# uacs-bottom.net
KiCad netlist of a schematic drawn in EAGLE
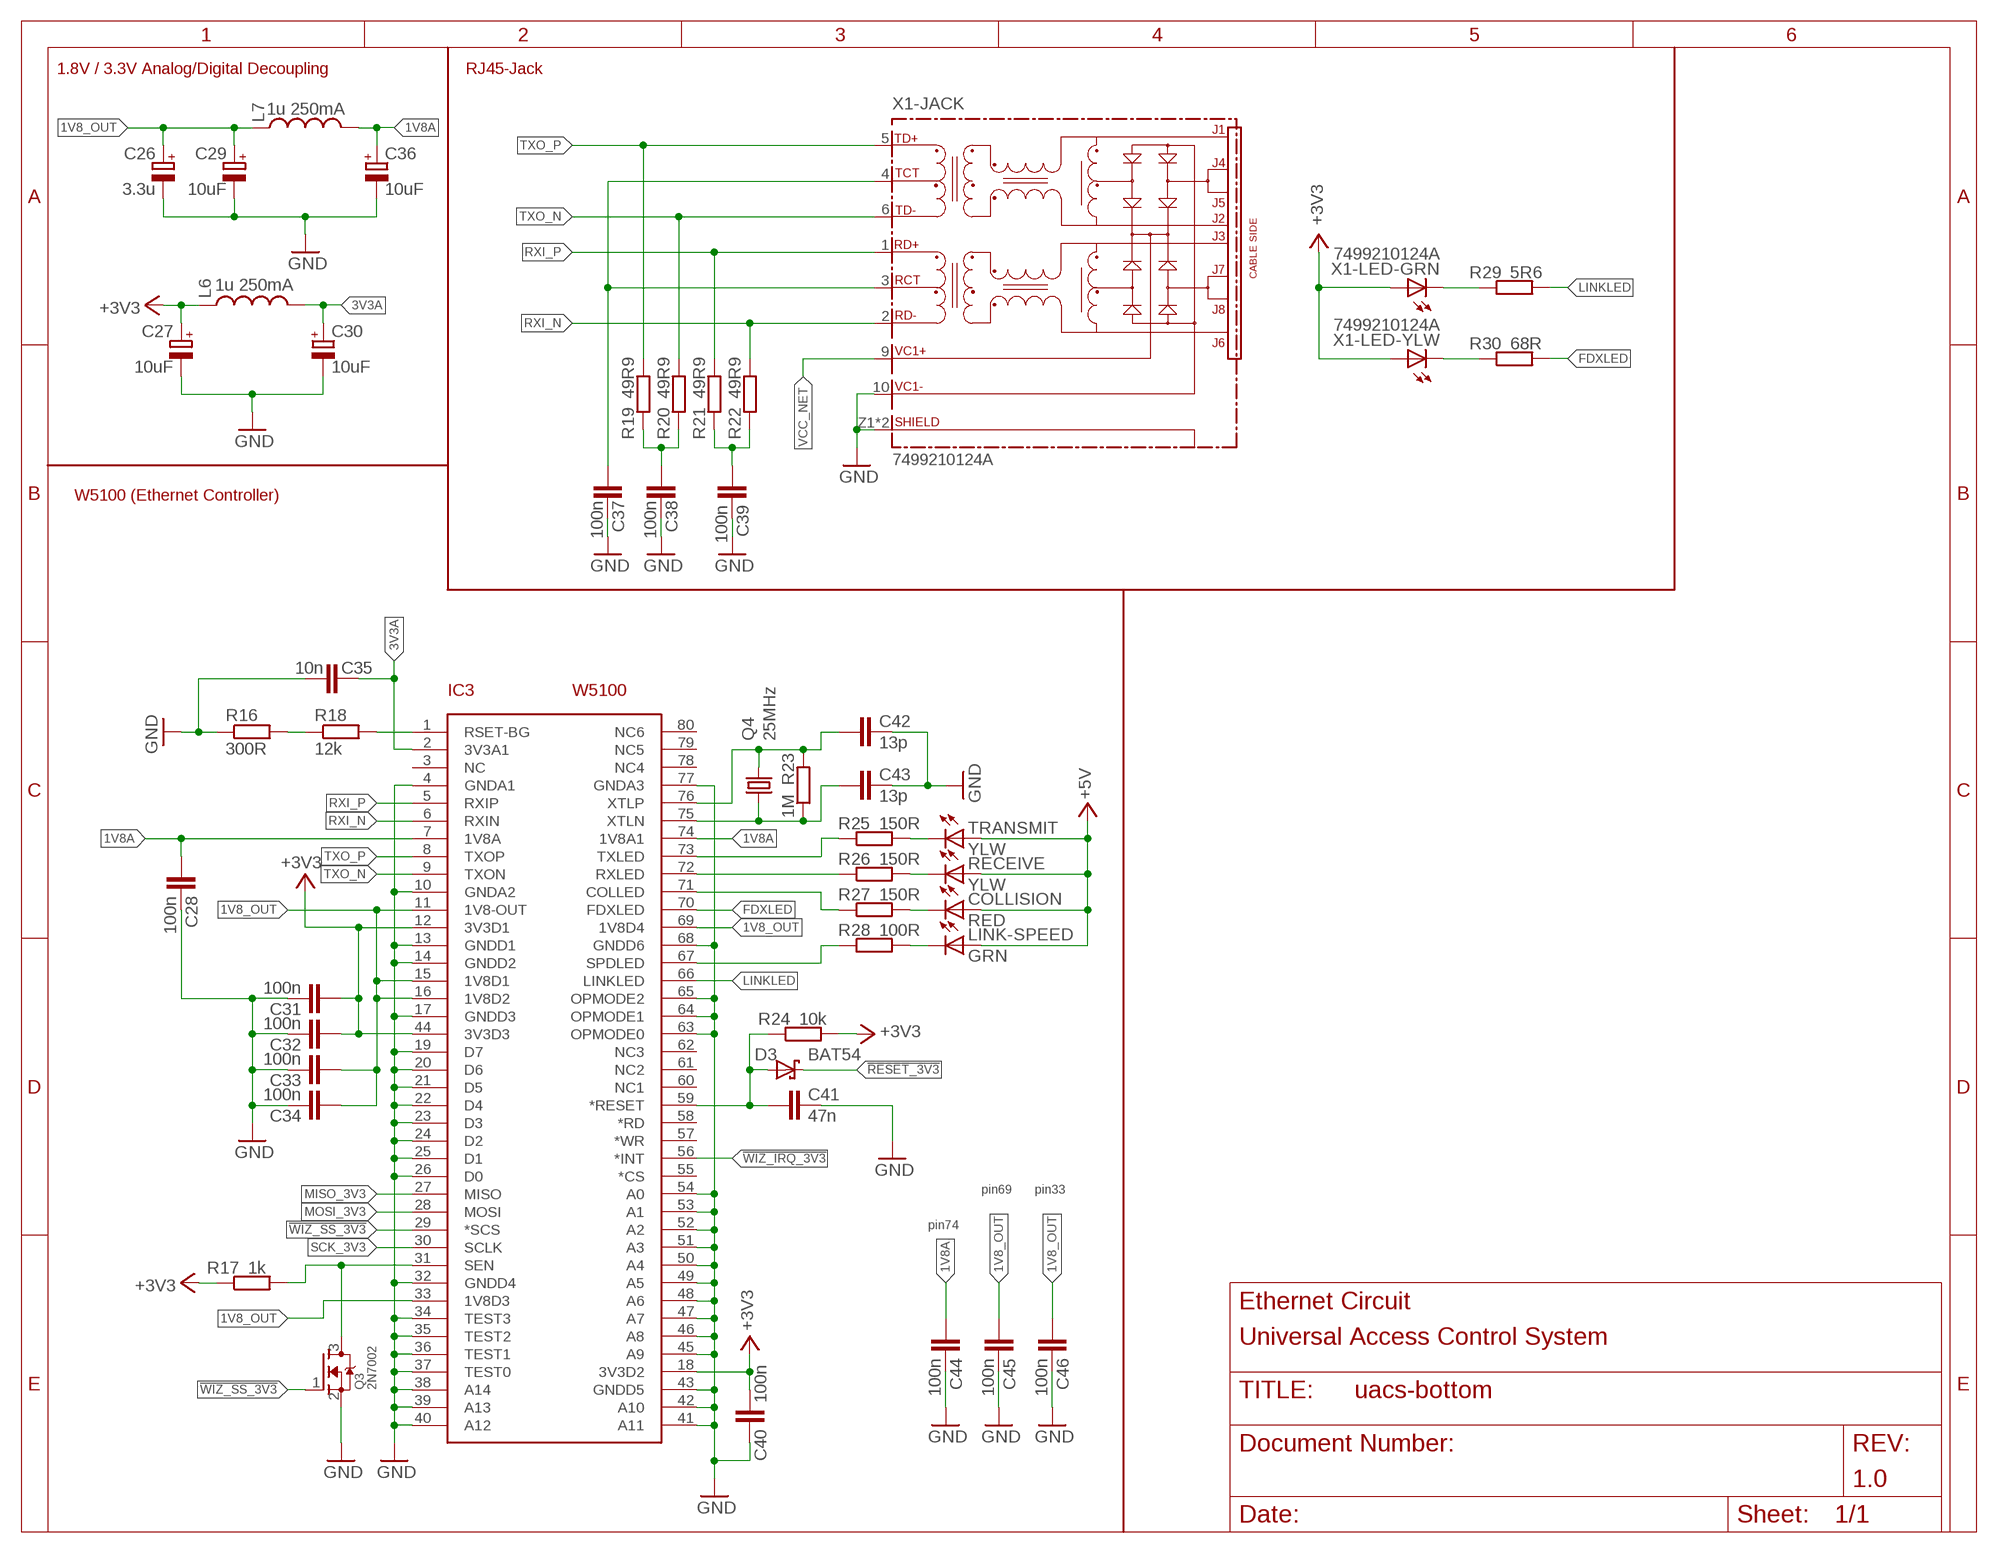
[diagram p0: schematic, sheet 1]

(export (version "E")
  (design (tool "Eeschema 10.0.6"))
  (components
    (comp (ref "C26")
      (value "3.3u")
      (footprint "eagle-import:B_3528-21R")
      (libsource (lib "eagle-import") (part "CPOL-EUB/3528-21R"))
    )
    (comp (ref "C27")
      (value "10uF")
      (footprint "eagle-import:B_3528-21R")
      (libsource (lib "eagle-import") (part "CPOL-EUB/3528-21R"))
    )
    (comp (ref "C28")
      (value "100n")
      (footprint "eagle-import:C0603")
      (libsource (lib "eagle-import") (part "C-EUC0603"))
    )
    (comp (ref "C29")
      (value "10uF")
      (footprint "eagle-import:B_3528-21R")
      (libsource (lib "eagle-import") (part "CPOL-EUB/3528-21R"))
    )
    (comp (ref "C30")
      (value "10uF")
      (footprint "eagle-import:B_3528-21R")
      (libsource (lib "eagle-import") (part "CPOL-EUB/3528-21R"))
    )
    (comp (ref "C31")
      (value "100n")
      (footprint "eagle-import:C0603")
      (libsource (lib "eagle-import") (part "C-EUC0603"))
    )
    (comp (ref "C32")
      (value "100n")
      (footprint "eagle-import:C0603")
      (libsource (lib "eagle-import") (part "C-EUC0603"))
    )
    (comp (ref "C33")
      (value "100n")
      (footprint "eagle-import:C0603")
      (libsource (lib "eagle-import") (part "C-EUC0603"))
    )
    (comp (ref "C34")
      (value "100n")
      (footprint "eagle-import:C0603")
      (libsource (lib "eagle-import") (part "C-EUC0603"))
    )
    (comp (ref "C35")
      (value "10n")
      (footprint "eagle-import:C0603")
      (libsource (lib "eagle-import") (part "C-EUC0603"))
    )
    (comp (ref "C36")
      (value "10uF")
      (footprint "eagle-import:B_3528-21R")
      (libsource (lib "eagle-import") (part "CPOL-EUB/3528-21R"))
    )
    (comp (ref "C37")
      (value "100n")
      (footprint "eagle-import:C0603")
      (libsource (lib "eagle-import") (part "C-EUC0603"))
    )
    (comp (ref "C38")
      (value "100n")
      (footprint "eagle-import:C0603")
      (libsource (lib "eagle-import") (part "C-EUC0603"))
    )
    (comp (ref "C39")
      (value "100n")
      (footprint "eagle-import:C0603")
      (libsource (lib "eagle-import") (part "C-EUC0603"))
    )
    (comp (ref "C40")
      (value "100n")
      (footprint "eagle-import:C0603")
      (libsource (lib "eagle-import") (part "C-EUC0603"))
    )
    (comp (ref "C41")
      (value "47n")
      (footprint "eagle-import:C0603")
      (libsource (lib "eagle-import") (part "C-EUC0603"))
    )
    (comp (ref "C42")
      (value "13p")
      (footprint "eagle-import:C0603")
      (libsource (lib "eagle-import") (part "C-EUC0603"))
    )
    (comp (ref "C43")
      (value "13p")
      (footprint "eagle-import:C0603")
      (libsource (lib "eagle-import") (part "C-EUC0603"))
    )
    (comp (ref "C44")
      (value "100n")
      (footprint "eagle-import:C0603")
      (libsource (lib "eagle-import") (part "C-EUC0603"))
    )
    (comp (ref "C45")
      (value "100n")
      (footprint "eagle-import:C0603")
      (libsource (lib "eagle-import") (part "C-EUC0603"))
    )
    (comp (ref "C46")
      (value "100n")
      (footprint "eagle-import:C0603")
      (libsource (lib "eagle-import") (part "C-EUC0603"))
    )
    (comp (ref "COLLISION")
      (value "RED")
      (footprint "eagle-import:CHIPLED_0603")
      (libsource (lib "eagle-import") (part "LEDCHIPLED_0603"))
    )
    (comp (ref "D3")
      (value "BAT54")
      (footprint "eagle-import:SOT23")
      (libsource (lib "eagle-import") (part "BAT54"))
    )
    (comp (ref "IC3")
      (value "W5100")
      (footprint "eagle-import:SQFP-S-10X10-80")
      (libsource (lib "eagle-import") (part "W5100"))
    )
    (comp (ref "L6")
      (value "1u 250mA")
      (footprint "eagle-import:0603")
      (libsource (lib "eagle-import") (part "INDUCTOR0603"))
    )
    (comp (ref "L7")
      (value "1u 250mA")
      (footprint "eagle-import:0603")
      (libsource (lib "eagle-import") (part "INDUCTOR0603"))
    )
    (comp (ref "LINK-SPEED")
      (value "GRN")
      (footprint "eagle-import:CHIPLED_0603")
      (libsource (lib "eagle-import") (part "LEDCHIPLED_0603"))
    )
    (comp (ref "Q3")
      (value "2N7002")
      (footprint "eagle-import:SOT23")
      (libsource (lib "eagle-import") (part "MOSFET-NREFLOW"))
    )
    (comp (ref "Q4")
      (value "25MHz")
      (footprint "eagle-import:SM49")
      (libsource (lib "eagle-import") (part "CRYSTALSM49"))
    )
    (comp (ref "R16")
      (value "300R")
      (footprint "eagle-import:R0603")
      (libsource (lib "eagle-import") (part "R-EU_R0603"))
    )
    (comp (ref "R17")
      (value "1k")
      (footprint "eagle-import:R0603")
      (libsource (lib "eagle-import") (part "R-EU_R0603"))
    )
    (comp (ref "R18")
      (value "12k")
      (footprint "eagle-import:R0603")
      (libsource (lib "eagle-import") (part "R-EU_R0603"))
    )
    (comp (ref "R19")
      (value "49R9")
      (footprint "eagle-import:R0603")
      (libsource (lib "eagle-import") (part "R-EU_R0603"))
    )
    (comp (ref "R20")
      (value "49R9")
      (footprint "eagle-import:R0603")
      (libsource (lib "eagle-import") (part "R-EU_R0603"))
    )
    (comp (ref "R21")
      (value "49R9")
      (footprint "eagle-import:R0603")
      (libsource (lib "eagle-import") (part "R-EU_R0603"))
    )
    (comp (ref "R22")
      (value "49R9")
      (footprint "eagle-import:R0603")
      (libsource (lib "eagle-import") (part "R-EU_R0603"))
    )
    (comp (ref "R23")
      (value "1M")
      (footprint "eagle-import:R0603")
      (libsource (lib "eagle-import") (part "R-EU_R0603"))
    )
    (comp (ref "R24")
      (value "10k")
      (footprint "eagle-import:R0603")
      (libsource (lib "eagle-import") (part "R-EU_R0603"))
    )
    (comp (ref "R25")
      (value "150R")
      (footprint "eagle-import:R0603")
      (libsource (lib "eagle-import") (part "R-EU_R0603"))
    )
    (comp (ref "R26")
      (value "150R")
      (footprint "eagle-import:R0603")
      (libsource (lib "eagle-import") (part "R-EU_R0603"))
    )
    (comp (ref "R27")
      (value "150R")
      (footprint "eagle-import:R0603")
      (libsource (lib "eagle-import") (part "R-EU_R0603"))
    )
    (comp (ref "R28")
      (value "100R")
      (footprint "eagle-import:R0603")
      (libsource (lib "eagle-import") (part "R-EU_R0603"))
    )
    (comp (ref "R29")
      (value "5R6")
      (footprint "eagle-import:R0603")
      (libsource (lib "eagle-import") (part "R-EU_R0603"))
    )
    (comp (ref "R30")
      (value "68R")
      (footprint "eagle-import:R0603")
      (libsource (lib "eagle-import") (part "R-EU_R0603"))
    )
    (comp (ref "RECEIVE")
      (value "YLW")
      (footprint "eagle-import:CHIPLED_0603")
      (libsource (lib "eagle-import") (part "LEDCHIPLED_0603"))
    )
    (comp (ref "TRANSMIT")
      (value "YLW")
      (footprint "eagle-import:CHIPLED_0603")
      (libsource (lib "eagle-import") (part "LEDCHIPLED_0603"))
    )
    (comp (ref "X1")
      (value "7499210124A")
      (footprint "eagle-import:7499210124A")
      (libsource (lib "eagle-import") (part "7499210124A"))
    )
  )
  (nets
    (net (code "1") (name "+3V3") (class "Default")
      (node (ref "C27") (pin "+") (pinfunction "+_+") (pintype "passive"))
      (node (ref "C31") (pin "1") (pinfunction "1_1") (pintype "passive"))
      (node (ref "C32") (pin "1") (pinfunction "1_1") (pintype "passive"))
      (node (ref "C40") (pin "1") (pinfunction "1_1") (pintype "passive"))
      (node (ref "IC3") (pin "12") (pinfunction "3V3D1_12") (pintype "power_in"))
      (node (ref "IC3") (pin "18") (pinfunction "3V3D2_18") (pintype "power_in"))
      (node (ref "IC3") (pin "44") (pinfunction "3V3D3_44") (pintype "power_in"))
      (node (ref "L6") (pin "1") (pinfunction "1_1") (pintype "passive"))
      (node (ref "R17") (pin "1") (pinfunction "1_1") (pintype "passive"))
      (node (ref "R24") (pin "2") (pinfunction "2_2") (pintype "passive"))
      (node (ref "X1") (pin "12") (pinfunction "A_12") (pintype "passive"))
      (node (ref "X1") (pin "14") (pinfunction "A_14") (pintype "passive"))
    )
    (net (code "2") (name "+5V") (class "Default")
      (node (ref "COLLISION") (pin "A") (pinfunction "A_A") (pintype "passive"))
      (node (ref "LINK-SPEED") (pin "A") (pinfunction "A_A") (pintype "passive"))
      (node (ref "RECEIVE") (pin "A") (pinfunction "A_A") (pintype "passive"))
      (node (ref "TRANSMIT") (pin "A") (pinfunction "A_A") (pintype "passive"))
    )
    (net (code "3") (name "/~{RESET_3V3}") (class "Default")
      (node (ref "D3") (pin "3") (pinfunction "C_3") (pintype "passive"))
    )
    (net (code "4") (name "/~{WIZ_IRQ_3V3}") (class "Default")
      (node (ref "IC3") (pin "56") (pinfunction "*INT_56") (pintype "input"))
    )
    (net (code "5") (name "/~{WIZ_SS_3V3}") (class "Default")
      (node (ref "IC3") (pin "29") (pinfunction "*SCS_29") (pintype "input"))
      (node (ref "Q3") (pin "1") (pinfunction "G_1") (pintype "bidirectional"))
    )
    (net (code "6") (name "1V8A") (class "Default")
      (node (ref "C28") (pin "1") (pinfunction "1_1") (pintype "passive"))
      (node (ref "C36") (pin "+") (pinfunction "+_+") (pintype "passive"))
      (node (ref "C44") (pin "1") (pinfunction "1_1") (pintype "passive"))
      (node (ref "IC3") (pin "7") (pinfunction "1V8A_7") (pintype "power_in"))
      (node (ref "IC3") (pin "74") (pinfunction "1V8A1_74") (pintype "power_in"))
      (node (ref "L7") (pin "2") (pinfunction "2_2") (pintype "passive"))
    )
    (net (code "7") (name "1V8_OUT") (class "Default")
      (node (ref "C26") (pin "+") (pinfunction "+_+") (pintype "passive"))
      (node (ref "C29") (pin "+") (pinfunction "+_+") (pintype "passive"))
      (node (ref "C33") (pin "1") (pinfunction "1_1") (pintype "passive"))
      (node (ref "C34") (pin "1") (pinfunction "1_1") (pintype "passive"))
      (node (ref "C45") (pin "1") (pinfunction "1_1") (pintype "passive"))
      (node (ref "C46") (pin "1") (pinfunction "1_1") (pintype "passive"))
      (node (ref "IC3") (pin "11") (pinfunction "1V8-OUT_11") (pintype "power_in"))
      (node (ref "IC3") (pin "15") (pinfunction "1V8D1_15") (pintype "power_in"))
      (node (ref "IC3") (pin "16") (pinfunction "1V8D2_16") (pintype "power_in"))
      (node (ref "IC3") (pin "33") (pinfunction "1V8D3_33") (pintype "power_in"))
      (node (ref "IC3") (pin "69") (pinfunction "1V8D4_69") (pintype "power_in"))
      (node (ref "L7") (pin "1") (pinfunction "1_1") (pintype "passive"))
    )
    (net (code "8") (name "3V3A") (class "Default")
      (node (ref "C30") (pin "+") (pinfunction "+_+") (pintype "passive"))
      (node (ref "C35") (pin "1") (pinfunction "1_1") (pintype "passive"))
      (node (ref "IC3") (pin "2") (pinfunction "3V3A1_2") (pintype "power_in"))
      (node (ref "L6") (pin "2") (pinfunction "2_2") (pintype "passive"))
    )
    (net (code "9") (name "FDXLED") (class "Default")
      (node (ref "IC3") (pin "70") (pinfunction "FDXLED_70") (pintype "output"))
      (node (ref "R30") (pin "2") (pinfunction "2_2") (pintype "passive"))
    )
    (net (code "10") (name "GND") (class "Default")
      (node (ref "C26") (pin "-") (pinfunction "-_-") (pintype "passive"))
      (node (ref "C27") (pin "-") (pinfunction "-_-") (pintype "passive"))
      (node (ref "C28") (pin "2") (pinfunction "2_2") (pintype "passive"))
      (node (ref "C29") (pin "-") (pinfunction "-_-") (pintype "passive"))
      (node (ref "C30") (pin "-") (pinfunction "-_-") (pintype "passive"))
      (node (ref "C31") (pin "2") (pinfunction "2_2") (pintype "passive"))
      (node (ref "C32") (pin "2") (pinfunction "2_2") (pintype "passive"))
      (node (ref "C33") (pin "2") (pinfunction "2_2") (pintype "passive"))
      (node (ref "C34") (pin "2") (pinfunction "2_2") (pintype "passive"))
      (node (ref "C35") (pin "2") (pinfunction "2_2") (pintype "passive"))
      (node (ref "C36") (pin "-") (pinfunction "-_-") (pintype "passive"))
      (node (ref "C37") (pin "2") (pinfunction "2_2") (pintype "passive"))
      (node (ref "C38") (pin "2") (pinfunction "2_2") (pintype "passive"))
      (node (ref "C39") (pin "2") (pinfunction "2_2") (pintype "passive"))
      (node (ref "C40") (pin "2") (pinfunction "2_2") (pintype "passive"))
      (node (ref "C41") (pin "2") (pinfunction "2_2") (pintype "passive"))
      (node (ref "C42") (pin "2") (pinfunction "2_2") (pintype "passive"))
      (node (ref "C43") (pin "2") (pinfunction "2_2") (pintype "passive"))
      (node (ref "C44") (pin "2") (pinfunction "2_2") (pintype "passive"))
      (node (ref "C45") (pin "2") (pinfunction "2_2") (pintype "passive"))
      (node (ref "C46") (pin "2") (pinfunction "2_2") (pintype "passive"))
      (node (ref "IC3") (pin "10") (pinfunction "GNDA2_10") (pintype "power_in"))
      (node (ref "IC3") (pin "13") (pinfunction "GNDD1_13") (pintype "power_in"))
      (node (ref "IC3") (pin "14") (pinfunction "GNDD2_14") (pintype "power_in"))
      (node (ref "IC3") (pin "17") (pinfunction "GNDD3_17") (pintype "power_in"))
      (node (ref "IC3") (pin "19") (pinfunction "D7_19") (pintype "input"))
      (node (ref "IC3") (pin "20") (pinfunction "D6_20") (pintype "input"))
      (node (ref "IC3") (pin "21") (pinfunction "D5_21") (pintype "input"))
      (node (ref "IC3") (pin "22") (pinfunction "D4_22") (pintype "input"))
      (node (ref "IC3") (pin "23") (pinfunction "D3_23") (pintype "input"))
      (node (ref "IC3") (pin "24") (pinfunction "D2_24") (pintype "input"))
      (node (ref "IC3") (pin "25") (pinfunction "D1_25") (pintype "input"))
      (node (ref "IC3") (pin "26") (pinfunction "D0_26") (pintype "input"))
      (node (ref "IC3") (pin "32") (pinfunction "GNDD4_32") (pintype "power_in"))
      (node (ref "IC3") (pin "34") (pinfunction "TEST3_34") (pintype "input"))
      (node (ref "IC3") (pin "35") (pinfunction "TEST2_35") (pintype "input"))
      (node (ref "IC3") (pin "36") (pinfunction "TEST1_36") (pintype "input"))
      (node (ref "IC3") (pin "37") (pinfunction "TEST0_37") (pintype "input"))
      (node (ref "IC3") (pin "38") (pinfunction "A14_38") (pintype "input"))
      (node (ref "IC3") (pin "39") (pinfunction "A13_39") (pintype "input"))
      (node (ref "IC3") (pin "4") (pinfunction "GNDA1_4") (pintype "power_in"))
      (node (ref "IC3") (pin "40") (pinfunction "A12_40") (pintype "input"))
      (node (ref "IC3") (pin "41") (pinfunction "A11_41") (pintype "input"))
      (node (ref "IC3") (pin "42") (pinfunction "A10_42") (pintype "input"))
      (node (ref "IC3") (pin "43") (pinfunction "GNDD5_43") (pintype "power_in"))
      (node (ref "IC3") (pin "45") (pinfunction "A9_45") (pintype "input"))
      (node (ref "IC3") (pin "46") (pinfunction "A8_46") (pintype "input"))
      (node (ref "IC3") (pin "47") (pinfunction "A7_47") (pintype "input"))
      (node (ref "IC3") (pin "48") (pinfunction "A6_48") (pintype "input"))
      (node (ref "IC3") (pin "49") (pinfunction "A5_49") (pintype "input"))
      (node (ref "IC3") (pin "50") (pinfunction "A4_50") (pintype "input"))
      (node (ref "IC3") (pin "51") (pinfunction "A3_51") (pintype "input"))
      (node (ref "IC3") (pin "52") (pinfunction "A2_52") (pintype "input"))
      (node (ref "IC3") (pin "53") (pinfunction "A1_53") (pintype "input"))
      (node (ref "IC3") (pin "54") (pinfunction "A0_54") (pintype "input"))
      (node (ref "IC3") (pin "63") (pinfunction "OPMODE0_63") (pintype "input"))
      (node (ref "IC3") (pin "64") (pinfunction "OPMODE1_64") (pintype "input"))
      (node (ref "IC3") (pin "65") (pinfunction "OPMODE2_65") (pintype "input"))
      (node (ref "IC3") (pin "68") (pinfunction "GNDD6_68") (pintype "power_in"))
      (node (ref "IC3") (pin "77") (pinfunction "GNDA3_77") (pintype "power_in"))
      (node (ref "Q3") (pin "2") (pinfunction "S_2") (pintype "bidirectional"))
      (node (ref "R16") (pin "1") (pinfunction "1_1") (pintype "passive"))
      (node (ref "X1") (pin "10") (pinfunction "VC1-_10") (pintype "power_in"))
      (node (ref "X1") (pin "Z1") (pinfunction "SHIELD_Z1") (pintype "bidirectional"))
      (node (ref "X1") (pin "Z2") (pinfunction "SHIELD_Z2") (pintype "bidirectional"))
    )
    (net (code "11") (name "LINKLED") (class "Default")
      (node (ref "IC3") (pin "66") (pinfunction "LINKLED_66") (pintype "output"))
      (node (ref "R29") (pin "2") (pinfunction "2_2") (pintype "passive"))
    )
    (net (code "12") (name "MISO_3V3") (class "Default")
      (node (ref "IC3") (pin "27") (pinfunction "MISO_27") (pintype "input"))
    )
    (net (code "13") (name "MOSI_3V3") (class "Default")
      (node (ref "IC3") (pin "28") (pinfunction "MOSI_28") (pintype "output"))
    )
    (net (code "14") (name "Net-(C38-Pad1)") (class "Default")
      (node (ref "C38") (pin "1") (pinfunction "1_1") (pintype "passive"))
      (node (ref "R19") (pin "1") (pinfunction "1_1") (pintype "passive"))
      (node (ref "R20") (pin "1") (pinfunction "1_1") (pintype "passive"))
    )
    (net (code "15") (name "Net-(C39-Pad1)") (class "Default")
      (node (ref "C39") (pin "1") (pinfunction "1_1") (pintype "passive"))
      (node (ref "R21") (pin "1") (pinfunction "1_1") (pintype "passive"))
      (node (ref "R22") (pin "1") (pinfunction "1_1") (pintype "passive"))
    )
    (net (code "16") (name "Net-(COLLISION-PadC)") (class "Default")
      (node (ref "COLLISION") (pin "C") (pinfunction "C_C") (pintype "passive"))
      (node (ref "R27") (pin "2") (pinfunction "2_2") (pintype "passive"))
    )
    (net (code "17") (name "Net-(D3-A)") (class "Default")
      (node (ref "C41") (pin "1") (pinfunction "1_1") (pintype "passive"))
      (node (ref "D3") (pin "1") (pinfunction "A_1") (pintype "passive"))
      (node (ref "IC3") (pin "59") (pinfunction "*RESET_59") (pintype "input"))
      (node (ref "R24") (pin "1") (pinfunction "1_1") (pintype "passive"))
    )
    (net (code "18") (name "Net-(IC3-COLLED)") (class "Default")
      (node (ref "IC3") (pin "71") (pinfunction "COLLED_71") (pintype "output"))
      (node (ref "R27") (pin "1") (pinfunction "1_1") (pintype "passive"))
    )
    (net (code "19") (name "Net-(IC3-RSET-BG)") (class "Default")
      (node (ref "IC3") (pin "1") (pinfunction "RSET-BG_1") (pintype "input"))
      (node (ref "R18") (pin "2") (pinfunction "2_2") (pintype "passive"))
    )
    (net (code "20") (name "Net-(IC3-RXLED)") (class "Default")
      (node (ref "IC3") (pin "72") (pinfunction "RXLED_72") (pintype "output"))
      (node (ref "R26") (pin "1") (pinfunction "1_1") (pintype "passive"))
    )
    (net (code "21") (name "Net-(IC3-SEN)") (class "Default")
      (node (ref "IC3") (pin "31") (pinfunction "SEN_31") (pintype "input"))
      (node (ref "Q3") (pin "3") (pinfunction "D_3") (pintype "bidirectional"))
      (node (ref "R17") (pin "2") (pinfunction "2_2") (pintype "passive"))
    )
    (net (code "22") (name "Net-(IC3-SPDLED)") (class "Default")
      (node (ref "IC3") (pin "67") (pinfunction "SPDLED_67") (pintype "output"))
      (node (ref "R28") (pin "1") (pinfunction "1_1") (pintype "passive"))
    )
    (net (code "23") (name "Net-(IC3-TXLED)") (class "Default")
      (node (ref "IC3") (pin "73") (pinfunction "TXLED_73") (pintype "output"))
      (node (ref "R25") (pin "1") (pinfunction "1_1") (pintype "passive"))
    )
    (net (code "24") (name "Net-(IC3-XTLN)") (class "Default")
      (node (ref "C43") (pin "1") (pinfunction "1_1") (pintype "passive"))
      (node (ref "IC3") (pin "75") (pinfunction "XTLN_75") (pintype "output"))
      (node (ref "Q4") (pin "1") (pinfunction "1_1") (pintype "passive"))
      (node (ref "R23") (pin "1") (pinfunction "1_1") (pintype "passive"))
    )
    (net (code "25") (name "Net-(IC3-XTLP)") (class "Default")
      (node (ref "C42") (pin "1") (pinfunction "1_1") (pintype "passive"))
      (node (ref "IC3") (pin "76") (pinfunction "XTLP_76") (pintype "output"))
      (node (ref "Q4") (pin "2") (pinfunction "2_2") (pintype "passive"))
      (node (ref "R23") (pin "2") (pinfunction "2_2") (pintype "passive"))
    )
    (net (code "26") (name "Net-(LINK-SPEED-PadC)") (class "Default")
      (node (ref "LINK-SPEED") (pin "C") (pinfunction "C_C") (pintype "passive"))
      (node (ref "R28") (pin "2") (pinfunction "2_2") (pintype "passive"))
    )
    (net (code "27") (name "Net-(R16-Pad2)") (class "Default")
      (node (ref "R16") (pin "2") (pinfunction "2_2") (pintype "passive"))
      (node (ref "R18") (pin "1") (pinfunction "1_1") (pintype "passive"))
    )
    (net (code "28") (name "Net-(R25-Pad2)") (class "Default")
      (node (ref "R25") (pin "2") (pinfunction "2_2") (pintype "passive"))
      (node (ref "TRANSMIT") (pin "C") (pinfunction "C_C") (pintype "passive"))
    )
    (net (code "29") (name "Net-(R26-Pad2)") (class "Default")
      (node (ref "R26") (pin "2") (pinfunction "2_2") (pintype "passive"))
      (node (ref "RECEIVE") (pin "C") (pinfunction "C_C") (pintype "passive"))
    )
    (net (code "30") (name "Net-(X1A-RCT)") (class "Default")
      (node (ref "C37") (pin "1") (pinfunction "1_1") (pintype "passive"))
      (node (ref "X1") (pin "3") (pinfunction "RCT_3") (pintype "bidirectional"))
      (node (ref "X1") (pin "4") (pinfunction "TCT_4") (pintype "bidirectional"))
    )
    (net (code "31") (name "Net-(X1B-C)") (class "Default")
      (node (ref "R29") (pin "1") (pinfunction "1_1") (pintype "passive"))
      (node (ref "X1") (pin "11") (pinfunction "C_11") (pintype "passive"))
    )
    (net (code "32") (name "Net-(X1C-C)") (class "Default")
      (node (ref "R30") (pin "1") (pinfunction "1_1") (pintype "passive"))
      (node (ref "X1") (pin "13") (pinfunction "C_13") (pintype "passive"))
    )
    (net (code "33") (name "RXI_N") (class "Default")
      (node (ref "IC3") (pin "6") (pinfunction "RXIN_6") (pintype "input"))
      (node (ref "R22") (pin "2") (pinfunction "2_2") (pintype "passive"))
      (node (ref "X1") (pin "2") (pinfunction "RD-_2") (pintype "bidirectional"))
    )
    (net (code "34") (name "RXI_P") (class "Default")
      (node (ref "IC3") (pin "5") (pinfunction "RXIP_5") (pintype "input"))
      (node (ref "R21") (pin "2") (pinfunction "2_2") (pintype "passive"))
      (node (ref "X1") (pin "1") (pinfunction "RD+_1") (pintype "bidirectional"))
    )
    (net (code "35") (name "SCK_3V3") (class "Default")
      (node (ref "IC3") (pin "30") (pinfunction "SCLK_30") (pintype "input"))
    )
    (net (code "36") (name "TXO_N") (class "Default")
      (node (ref "IC3") (pin "9") (pinfunction "TXON_9") (pintype "output"))
      (node (ref "R20") (pin "2") (pinfunction "2_2") (pintype "passive"))
      (node (ref "X1") (pin "6") (pinfunction "TD-_6") (pintype "bidirectional"))
    )
    (net (code "37") (name "TXO_P") (class "Default")
      (node (ref "IC3") (pin "8") (pinfunction "TXOP_8") (pintype "output"))
      (node (ref "R19") (pin "2") (pinfunction "2_2") (pintype "passive"))
      (node (ref "X1") (pin "5") (pinfunction "TD+_5") (pintype "bidirectional"))
    )
    (net (code "38") (name "VCC_NET") (class "Default")
      (node (ref "X1") (pin "9") (pinfunction "VC1+_9") (pintype "power_in"))
    )
    (net (code "39") (name "unconnected-(IC3-*CS-Pad55)") (class "Default")
      (node (ref "IC3") (pin "55") (pinfunction "*CS_55") (pintype "input"))
    )
    (net (code "40") (name "unconnected-(IC3-*RD-Pad58)") (class "Default")
      (node (ref "IC3") (pin "58") (pinfunction "*RD_58") (pintype "input"))
    )
    (net (code "41") (name "unconnected-(IC3-*WR-Pad57)") (class "Default")
      (node (ref "IC3") (pin "57") (pinfunction "*WR_57") (pintype "input"))
    )
    (net (code "42") (name "unconnected-(IC3-NC-Pad3)") (class "Default")
      (node (ref "IC3") (pin "3") (pinfunction "NC_3") (pintype "no_connect"))
    )
    (net (code "43") (name "unconnected-(IC3-NC1-Pad60)") (class "Default")
      (node (ref "IC3") (pin "60") (pinfunction "NC1_60") (pintype "no_connect"))
    )
    (net (code "44") (name "unconnected-(IC3-NC2-Pad61)") (class "Default")
      (node (ref "IC3") (pin "61") (pinfunction "NC2_61") (pintype "no_connect"))
    )
    (net (code "45") (name "unconnected-(IC3-NC3-Pad62)") (class "Default")
      (node (ref "IC3") (pin "62") (pinfunction "NC3_62") (pintype "no_connect"))
    )
    (net (code "46") (name "unconnected-(IC3-NC4-Pad78)") (class "Default")
      (node (ref "IC3") (pin "78") (pinfunction "NC4_78") (pintype "no_connect"))
    )
    (net (code "47") (name "unconnected-(IC3-NC5-Pad79)") (class "Default")
      (node (ref "IC3") (pin "79") (pinfunction "NC5_79") (pintype "no_connect"))
    )
    (net (code "48") (name "unconnected-(IC3-NC6-Pad80)") (class "Default")
      (node (ref "IC3") (pin "80") (pinfunction "NC6_80") (pintype "no_connect"))
    )
  )
)
